# CoProcessor.net
KiCad netlist of a schematic drawn in Altium Designer
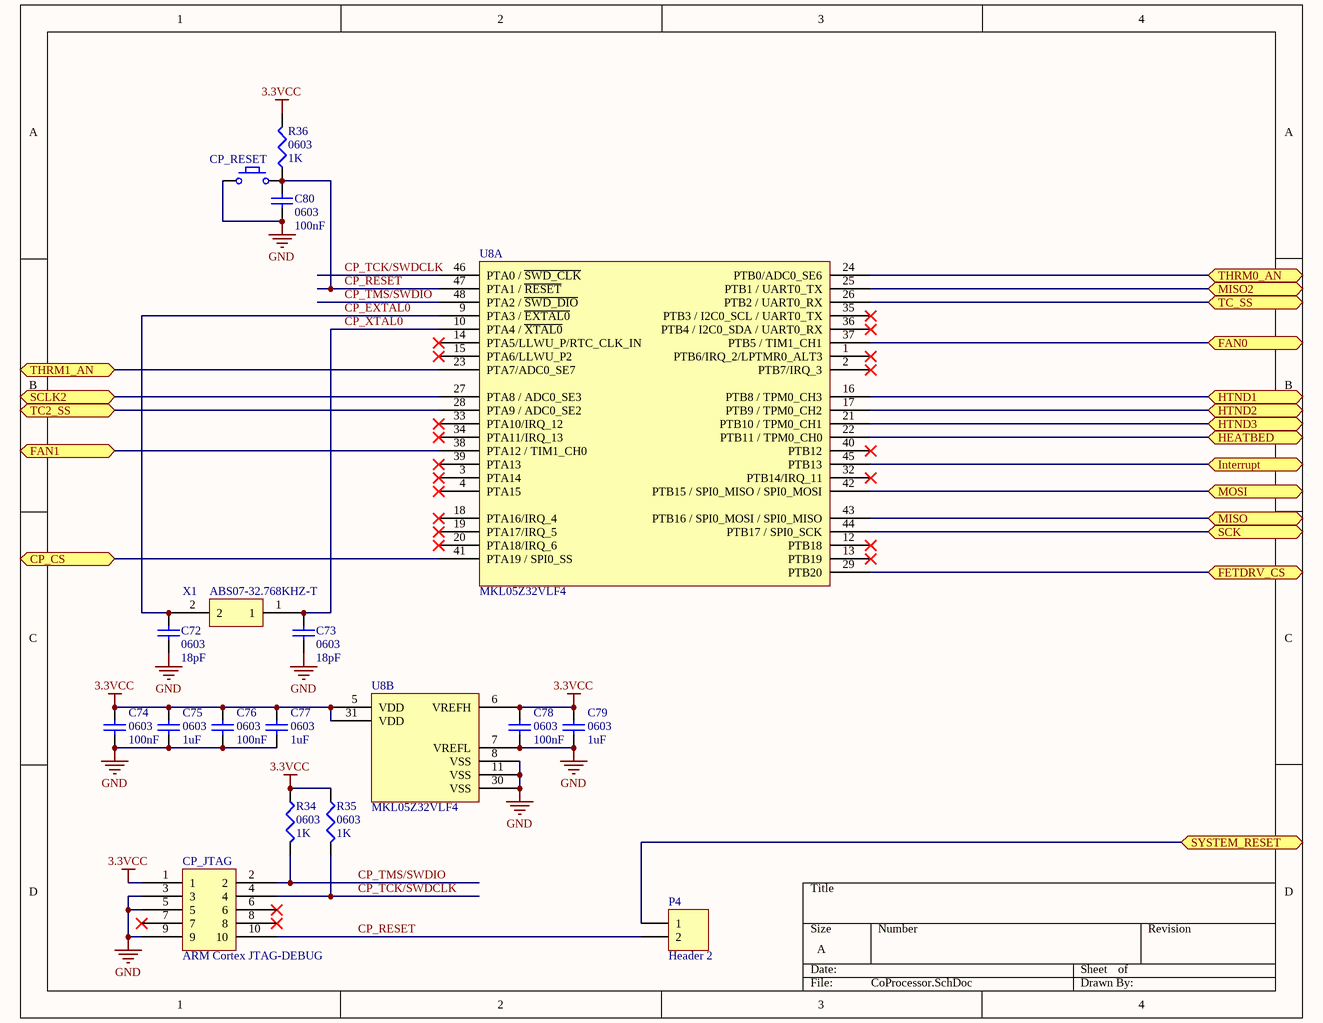
[diagram p0: CoProcessor.SchDoc]

(export (version "E")
  (design (tool "Eeschema 10.0.6"))
  (components
    (comp (ref "C72")
      (value "0603")
      (footprint "1608[0603]")
      (description "Capacitor (Semiconductor SIM Model)")
      (fields (field (name "ALTIUM_VALUE") "18pF") (field (name "PUBLISHER") "Altium Limited"))
      (libsource (lib "Miscellaneous Devices") (part "Cap Semi"))
    )
    (comp (ref "C73")
      (value "0603")
      (footprint "1608[0603]")
      (description "Capacitor (Semiconductor SIM Model)")
      (fields (field (name "ALTIUM_VALUE") "18pF") (field (name "PUBLISHER") "Altium Limited"))
      (libsource (lib "Miscellaneous Devices") (part "Cap Semi"))
    )
    (comp (ref "C74")
      (value "0603")
      (footprint "1608[0603]")
      (description "Capacitor (Semiconductor SIM Model)")
      (fields (field (name "ALTIUM_VALUE") "100nF") (field (name "PUBLISHER") "Altium Limited"))
      (libsource (lib "Miscellaneous Devices") (part "Cap Semi"))
    )
    (comp (ref "C75")
      (value "0603")
      (footprint "1608[0603]")
      (description "Capacitor (Semiconductor SIM Model)")
      (fields (field (name "ALTIUM_VALUE") "1uF") (field (name "PUBLISHER") "Altium Limited"))
      (libsource (lib "Miscellaneous Devices") (part "Cap Semi"))
    )
    (comp (ref "C76")
      (value "0603")
      (footprint "1608[0603]")
      (description "Capacitor (Semiconductor SIM Model)")
      (fields (field (name "ALTIUM_VALUE") "100nF") (field (name "PUBLISHER") "Altium Limited"))
      (libsource (lib "Miscellaneous Devices") (part "Cap Semi"))
    )
    (comp (ref "C77")
      (value "0603")
      (footprint "1608[0603]")
      (description "Capacitor (Semiconductor SIM Model)")
      (fields (field (name "ALTIUM_VALUE") "1uF") (field (name "PUBLISHER") "Altium Limited"))
      (libsource (lib "Miscellaneous Devices") (part "Cap Semi"))
    )
    (comp (ref "C78")
      (value "0603")
      (footprint "1608[0603]")
      (description "Capacitor (Semiconductor SIM Model)")
      (fields (field (name "ALTIUM_VALUE") "100nF") (field (name "PUBLISHER") "Altium Limited"))
      (libsource (lib "Miscellaneous Devices") (part "Cap Semi"))
    )
    (comp (ref "C79")
      (value "0603")
      (footprint "1608[0603]")
      (description "Capacitor (Semiconductor SIM Model)")
      (fields (field (name "ALTIUM_VALUE") "1uF") (field (name "PUBLISHER") "Altium Limited"))
      (libsource (lib "Miscellaneous Devices") (part "Cap Semi"))
    )
    (comp (ref "C80")
      (value "0603")
      (footprint "1608[0603]")
      (description "Capacitor (Semiconductor SIM Model)")
      (fields (field (name "ALTIUM_VALUE") "100nF") (field (name "PUBLISHER") "Altium Limited"))
      (libsource (lib "Miscellaneous Devices") (part "Cap Semi"))
    )
    (comp (ref "CP_JTAG")
      (value "ARM Cortex JTAG-DEBUG")
      (footprint "FTSH-105-XX-X-DV")
      (libsource (lib "Adams Altium Library") (part "ARM Cortex JTAG-DEBUG Header"))
    )
    (comp (ref "CP_RESET")
      (value "Tactile Switch")
      (footprint "Mountain Switch TS6324T1607")
      (libsource (lib "Adams Altium Library") (part "Tactile Switch"))
    )
    (comp (ref "P4")
      (value "Header 2")
      (footprint "HDR1X2")
      (description "Header, 2-Pin")
      (fields (field (name "PUBLISHER") "Altium Limited"))
      (libsource (lib "Miscellaneous Connectors") (part "Header 2"))
    )
    (comp (ref "R34")
      (value "0603")
      (footprint "J1-0603")
      (description "Resistor")
      (fields (field (name "ALTIUM_VALUE") "1K") (field (name "PUBLISHER") "Altium Limited"))
      (libsource (lib "Miscellaneous Devices") (part "Res3"))
    )
    (comp (ref "R35")
      (value "0603")
      (footprint "J1-0603")
      (description "Resistor")
      (fields (field (name "ALTIUM_VALUE") "1K") (field (name "PUBLISHER") "Altium Limited"))
      (libsource (lib "Miscellaneous Devices") (part "Res3"))
    )
    (comp (ref "R36")
      (value "0603")
      (footprint "J1-0603")
      (description "Resistor")
      (fields (field (name "ALTIUM_VALUE") "1K") (field (name "PUBLISHER") "Altium Limited"))
      (libsource (lib "Miscellaneous Devices") (part "Res3"))
    )
    (comp (ref "U8")
      (value "MKL05Z32VLF4")
      (footprint "MKL05Z32VLF4")
      (description "ARM Cortex M0+")
      (libsource (lib "ZMBo Schematic Library") (part "MKL05Z32VLF4"))
    )
    (comp (ref "X1")
      (value "ABS07-32.768KHZ-T")
      (footprint "ABS07-32.768KHZ-T")
      (description "ABS07-32.768KHZ-T RTC Crystal Oscillator")
      (libsource (lib "Adams Altium Library") (part "ABS07-32.768KHZ-T"))
    )
  )
  (nets
    (net (code "1") (name "/CP_CS") (class "Default")
      (node (ref "U8") (pin "41") (pinfunction "PTA19_/_SPI0_SS_41") (pintype "passive"))
    )
    (net (code "2") (name "/CP_EXTAL0") (class "Default")
      (node (ref "C72") (pin "1") (pinfunction "1_1") (pintype "passive"))
      (node (ref "U8") (pin "9") (pinfunction "PTA3_/_~{EXTAL0}_9") (pintype "passive"))
      (node (ref "X1") (pin "2") (pinfunction "2_2") (pintype "passive"))
    )
    (net (code "3") (name "/CP_RESET") (class "Default")
      (node (ref "C80") (pin "1") (pinfunction "1_1") (pintype "passive"))
      (node (ref "CP_JTAG") (pin "10") (pinfunction "10_10") (pintype "passive"))
      (node (ref "CP_RESET") (pin "2") (pintype "passive"))
      (node (ref "P4") (pin "2") (pinfunction "2_2") (pintype "passive"))
      (node (ref "R36") (pin "1") (pinfunction "1_1") (pintype "passive"))
      (node (ref "U8") (pin "47") (pinfunction "PTA1_/_~{RESET}_47") (pintype "passive"))
    )
    (net (code "4") (name "/CP_TCK{slash}SWDCLK") (class "Default")
      (node (ref "CP_JTAG") (pin "4") (pinfunction "4_4") (pintype "passive"))
      (node (ref "R35") (pin "2") (pinfunction "2_2") (pintype "passive"))
      (node (ref "U8") (pin "46") (pinfunction "PTA0_/_~{SWD_CLK}_46") (pintype "passive"))
    )
    (net (code "5") (name "/CP_TMS{slash}SWDIO") (class "Default")
      (node (ref "CP_JTAG") (pin "2") (pinfunction "2_2") (pintype "passive"))
      (node (ref "R34") (pin "2") (pinfunction "2_2") (pintype "passive"))
      (node (ref "U8") (pin "48") (pinfunction "PTA2_/_~{SWD_DIO}_48") (pintype "passive"))
    )
    (net (code "6") (name "/CP_XTAL0") (class "Default")
      (node (ref "C73") (pin "1") (pinfunction "1_1") (pintype "passive"))
      (node (ref "U8") (pin "10") (pinfunction "PTA4_/_~{XTAL0}_10") (pintype "passive"))
      (node (ref "X1") (pin "1") (pinfunction "1_1") (pintype "passive"))
    )
    (net (code "7") (name "/FAN0") (class "Default")
      (node (ref "U8") (pin "37") (pinfunction "PTB5_/_TIM1_CH1_37") (pintype "passive"))
    )
    (net (code "8") (name "/FAN1") (class "Default")
      (node (ref "U8") (pin "38") (pinfunction "PTA12_/_TIM1_CH0_38") (pintype "passive"))
    )
    (net (code "9") (name "/FETDRV_CS") (class "Default")
      (node (ref "U8") (pin "29") (pinfunction "PTB20_29") (pintype "passive"))
    )
    (net (code "10") (name "/HEATBED") (class "Default")
      (node (ref "U8") (pin "22") (pinfunction "PTB11_/_TPM0_CH0_22") (pintype "passive"))
    )
    (net (code "11") (name "/HTND1") (class "Default")
      (node (ref "U8") (pin "16") (pinfunction "PTB8_/_TPM0_CH3_16") (pintype "passive"))
    )
    (net (code "12") (name "/HTND2") (class "Default")
      (node (ref "U8") (pin "17") (pinfunction "PTB9_/_TPM0_CH2_17") (pintype "passive"))
    )
    (net (code "13") (name "/HTND3") (class "Default")
      (node (ref "U8") (pin "21") (pinfunction "PTB10_/_TPM0_CH1_21") (pintype "passive"))
    )
    (net (code "14") (name "/Interrupt") (class "Default")
      (node (ref "U8") (pin "45") (pinfunction "PTB13_45") (pintype "passive"))
    )
    (net (code "15") (name "/MISO") (class "Default")
      (node (ref "U8") (pin "43") (pinfunction "PTB16_/_SPI0_MOSI_/_SPI0_MISO_43") (pintype "passive"))
    )
    (net (code "16") (name "/MISO2") (class "Default")
      (node (ref "U8") (pin "25") (pinfunction "PTB1_/_UART0_TX_25") (pintype "passive"))
    )
    (net (code "17") (name "/MOSI") (class "Default")
      (node (ref "U8") (pin "42") (pinfunction "PTB15_/_SPI0_MISO_/_SPI0_MOSI_42") (pintype "passive"))
    )
    (net (code "18") (name "/SCK") (class "Default")
      (node (ref "U8") (pin "44") (pinfunction "PTB17_/_SPI0_SCK_44") (pintype "passive"))
    )
    (net (code "19") (name "/SCLK2") (class "Default")
      (node (ref "U8") (pin "27") (pinfunction "PTA8_/_ADC0_SE3_27") (pintype "passive"))
    )
    (net (code "20") (name "/SYSTEM_RESET") (class "Default")
      (node (ref "P4") (pin "1") (pinfunction "1_1") (pintype "passive"))
    )
    (net (code "21") (name "/TC2_SS") (class "Default")
      (node (ref "U8") (pin "28") (pinfunction "PTA9_/_ADC0_SE2_28") (pintype "passive"))
    )
    (net (code "22") (name "/TC_SS") (class "Default")
      (node (ref "U8") (pin "26") (pinfunction "PTB2_/_UART0_RX_26") (pintype "passive"))
    )
    (net (code "23") (name "/THRM0_AN") (class "Default")
      (node (ref "U8") (pin "24") (pinfunction "PTB0/ADC0_SE6_24") (pintype "passive"))
    )
    (net (code "24") (name "/THRM1_AN") (class "Default")
      (node (ref "U8") (pin "23") (pinfunction "PTA7/ADC0_SE7_23") (pintype "passive"))
    )
    (net (code "25") (name "3.3VCC") (class "Default")
      (node (ref "C74") (pin "2") (pinfunction "2_2") (pintype "passive"))
      (node (ref "C75") (pin "2") (pinfunction "2_2") (pintype "passive"))
      (node (ref "C76") (pin "2") (pinfunction "2_2") (pintype "passive"))
      (node (ref "C77") (pin "2") (pinfunction "2_2") (pintype "passive"))
      (node (ref "C78") (pin "1") (pinfunction "1_1") (pintype "passive"))
      (node (ref "C79") (pin "1") (pinfunction "1_1") (pintype "passive"))
      (node (ref "CP_JTAG") (pin "1") (pinfunction "1_1") (pintype "passive"))
      (node (ref "R34") (pin "1") (pinfunction "1_1") (pintype "passive"))
      (node (ref "R35") (pin "1") (pinfunction "1_1") (pintype "passive"))
      (node (ref "R36") (pin "2") (pinfunction "2_2") (pintype "passive"))
      (node (ref "U8") (pin "31") (pinfunction "VDD_31") (pintype "passive"))
      (node (ref "U8") (pin "5") (pinfunction "VDD_5") (pintype "passive"))
      (node (ref "U8") (pin "6") (pinfunction "VREFH_6") (pintype "passive"))
    )
    (net (code "26") (name "GND") (class "Default")
      (node (ref "C72") (pin "2") (pinfunction "2_2") (pintype "passive"))
      (node (ref "C73") (pin "2") (pinfunction "2_2") (pintype "passive"))
      (node (ref "C74") (pin "1") (pinfunction "1_1") (pintype "passive"))
      (node (ref "C75") (pin "1") (pinfunction "1_1") (pintype "passive"))
      (node (ref "C76") (pin "1") (pinfunction "1_1") (pintype "passive"))
      (node (ref "C77") (pin "1") (pinfunction "1_1") (pintype "passive"))
      (node (ref "C78") (pin "2") (pinfunction "2_2") (pintype "passive"))
      (node (ref "C79") (pin "2") (pinfunction "2_2") (pintype "passive"))
      (node (ref "C80") (pin "2") (pinfunction "2_2") (pintype "passive"))
      (node (ref "CP_JTAG") (pin "3") (pinfunction "3_3") (pintype "passive"))
      (node (ref "CP_JTAG") (pin "5") (pinfunction "5_5") (pintype "passive"))
      (node (ref "CP_JTAG") (pin "9") (pinfunction "9_9") (pintype "passive"))
      (node (ref "CP_RESET") (pin "1") (pintype "passive"))
      (node (ref "U8") (pin "11") (pinfunction "VSS_11") (pintype "passive"))
      (node (ref "U8") (pin "30") (pinfunction "VSS_30") (pintype "passive"))
      (node (ref "U8") (pin "7") (pinfunction "VREFL_7") (pintype "passive"))
      (node (ref "U8") (pin "8") (pinfunction "VSS_8") (pintype "passive"))
    )
    (net (code "27") (name "unconnected-(CP_JTAG-Pad6)") (class "Default")
      (node (ref "CP_JTAG") (pin "6") (pinfunction "6_6") (pintype "passive+no_connect"))
    )
    (net (code "28") (name "unconnected-(CP_JTAG-Pad7)") (class "Default")
      (node (ref "CP_JTAG") (pin "7") (pinfunction "7_7") (pintype "passive+no_connect"))
    )
    (net (code "29") (name "unconnected-(CP_JTAG-Pad8)") (class "Default")
      (node (ref "CP_JTAG") (pin "8") (pinfunction "8_8") (pintype "passive+no_connect"))
    )
    (net (code "30") (name "unconnected-(U8A-PTA5{slash}LLWU_P{slash}RTC_CLK_IN-Pad14)") (class "Default")
      (node (ref "U8") (pin "14") (pinfunction "PTA5/LLWU_P/RTC_CLK_IN_14") (pintype "passive+no_connect"))
    )
    (net (code "31") (name "unconnected-(U8A-PTA6{slash}LLWU_P2-Pad15)") (class "Default")
      (node (ref "U8") (pin "15") (pinfunction "PTA6/LLWU_P2_15") (pintype "passive+no_connect"))
    )
    (net (code "32") (name "unconnected-(U8A-PTA10{slash}IRQ_12-Pad33)") (class "Default")
      (node (ref "U8") (pin "33") (pinfunction "PTA10/IRQ_12_33") (pintype "passive+no_connect"))
    )
    (net (code "33") (name "unconnected-(U8A-PTA11{slash}IRQ_13-Pad34)") (class "Default")
      (node (ref "U8") (pin "34") (pinfunction "PTA11/IRQ_13_34") (pintype "passive+no_connect"))
    )
    (net (code "34") (name "unconnected-(U8A-PTA13-Pad39)") (class "Default")
      (node (ref "U8") (pin "39") (pinfunction "PTA13_39") (pintype "passive+no_connect"))
    )
    (net (code "35") (name "unconnected-(U8A-PTA14-Pad3)") (class "Default")
      (node (ref "U8") (pin "3") (pinfunction "PTA14_3") (pintype "passive+no_connect"))
    )
    (net (code "36") (name "unconnected-(U8A-PTA15-Pad4)") (class "Default")
      (node (ref "U8") (pin "4") (pinfunction "PTA15_4") (pintype "passive+no_connect"))
    )
    (net (code "37") (name "unconnected-(U8A-PTA16{slash}IRQ_4-Pad18)") (class "Default")
      (node (ref "U8") (pin "18") (pinfunction "PTA16/IRQ_4_18") (pintype "passive+no_connect"))
    )
    (net (code "38") (name "unconnected-(U8A-PTA17{slash}IRQ_5-Pad19)") (class "Default")
      (node (ref "U8") (pin "19") (pinfunction "PTA17/IRQ_5_19") (pintype "passive+no_connect"))
    )
    (net (code "39") (name "unconnected-(U8A-PTA18{slash}IRQ_6-Pad20)") (class "Default")
      (node (ref "U8") (pin "20") (pinfunction "PTA18/IRQ_6_20") (pintype "passive+no_connect"))
    )
    (net (code "40") (name "unconnected-(U8A-PTB3_{slash}_I2C0_SCL_{slash}_UART0_TX-Pad35)") (class "Default")
      (node (ref "U8") (pin "35") (pinfunction "PTB3_/_I2C0_SCL_/_UART0_TX_35") (pintype "passive+no_connect"))
    )
    (net (code "41") (name "unconnected-(U8A-PTB4_{slash}_I2C0_SDA_{slash}_UART0_RX-Pad36)") (class "Default")
      (node (ref "U8") (pin "36") (pinfunction "PTB4_/_I2C0_SDA_/_UART0_RX_36") (pintype "passive+no_connect"))
    )
    (net (code "42") (name "unconnected-(U8A-PTB6{slash}IRQ_2{slash}LPTMR0_ALT3-Pad1)") (class "Default")
      (node (ref "U8") (pin "1") (pinfunction "PTB6/IRQ_2/LPTMR0_ALT3_1") (pintype "passive+no_connect"))
    )
    (net (code "43") (name "unconnected-(U8A-PTB7{slash}IRQ_3-Pad2)") (class "Default")
      (node (ref "U8") (pin "2") (pinfunction "PTB7/IRQ_3_2") (pintype "passive+no_connect"))
    )
    (net (code "44") (name "unconnected-(U8A-PTB12-Pad40)") (class "Default")
      (node (ref "U8") (pin "40") (pinfunction "PTB12_40") (pintype "passive+no_connect"))
    )
    (net (code "45") (name "unconnected-(U8A-PTB14{slash}IRQ_11-Pad32)") (class "Default")
      (node (ref "U8") (pin "32") (pinfunction "PTB14/IRQ_11_32") (pintype "passive+no_connect"))
    )
    (net (code "46") (name "unconnected-(U8A-PTB18-Pad12)") (class "Default")
      (node (ref "U8") (pin "12") (pinfunction "PTB18_12") (pintype "passive+no_connect"))
    )
    (net (code "47") (name "unconnected-(U8A-PTB19-Pad13)") (class "Default")
      (node (ref "U8") (pin "13") (pinfunction "PTB19_13") (pintype "passive+no_connect"))
    )
  )
)
